# Power.net
KiCad netlist of a schematic drawn in Altium Designer
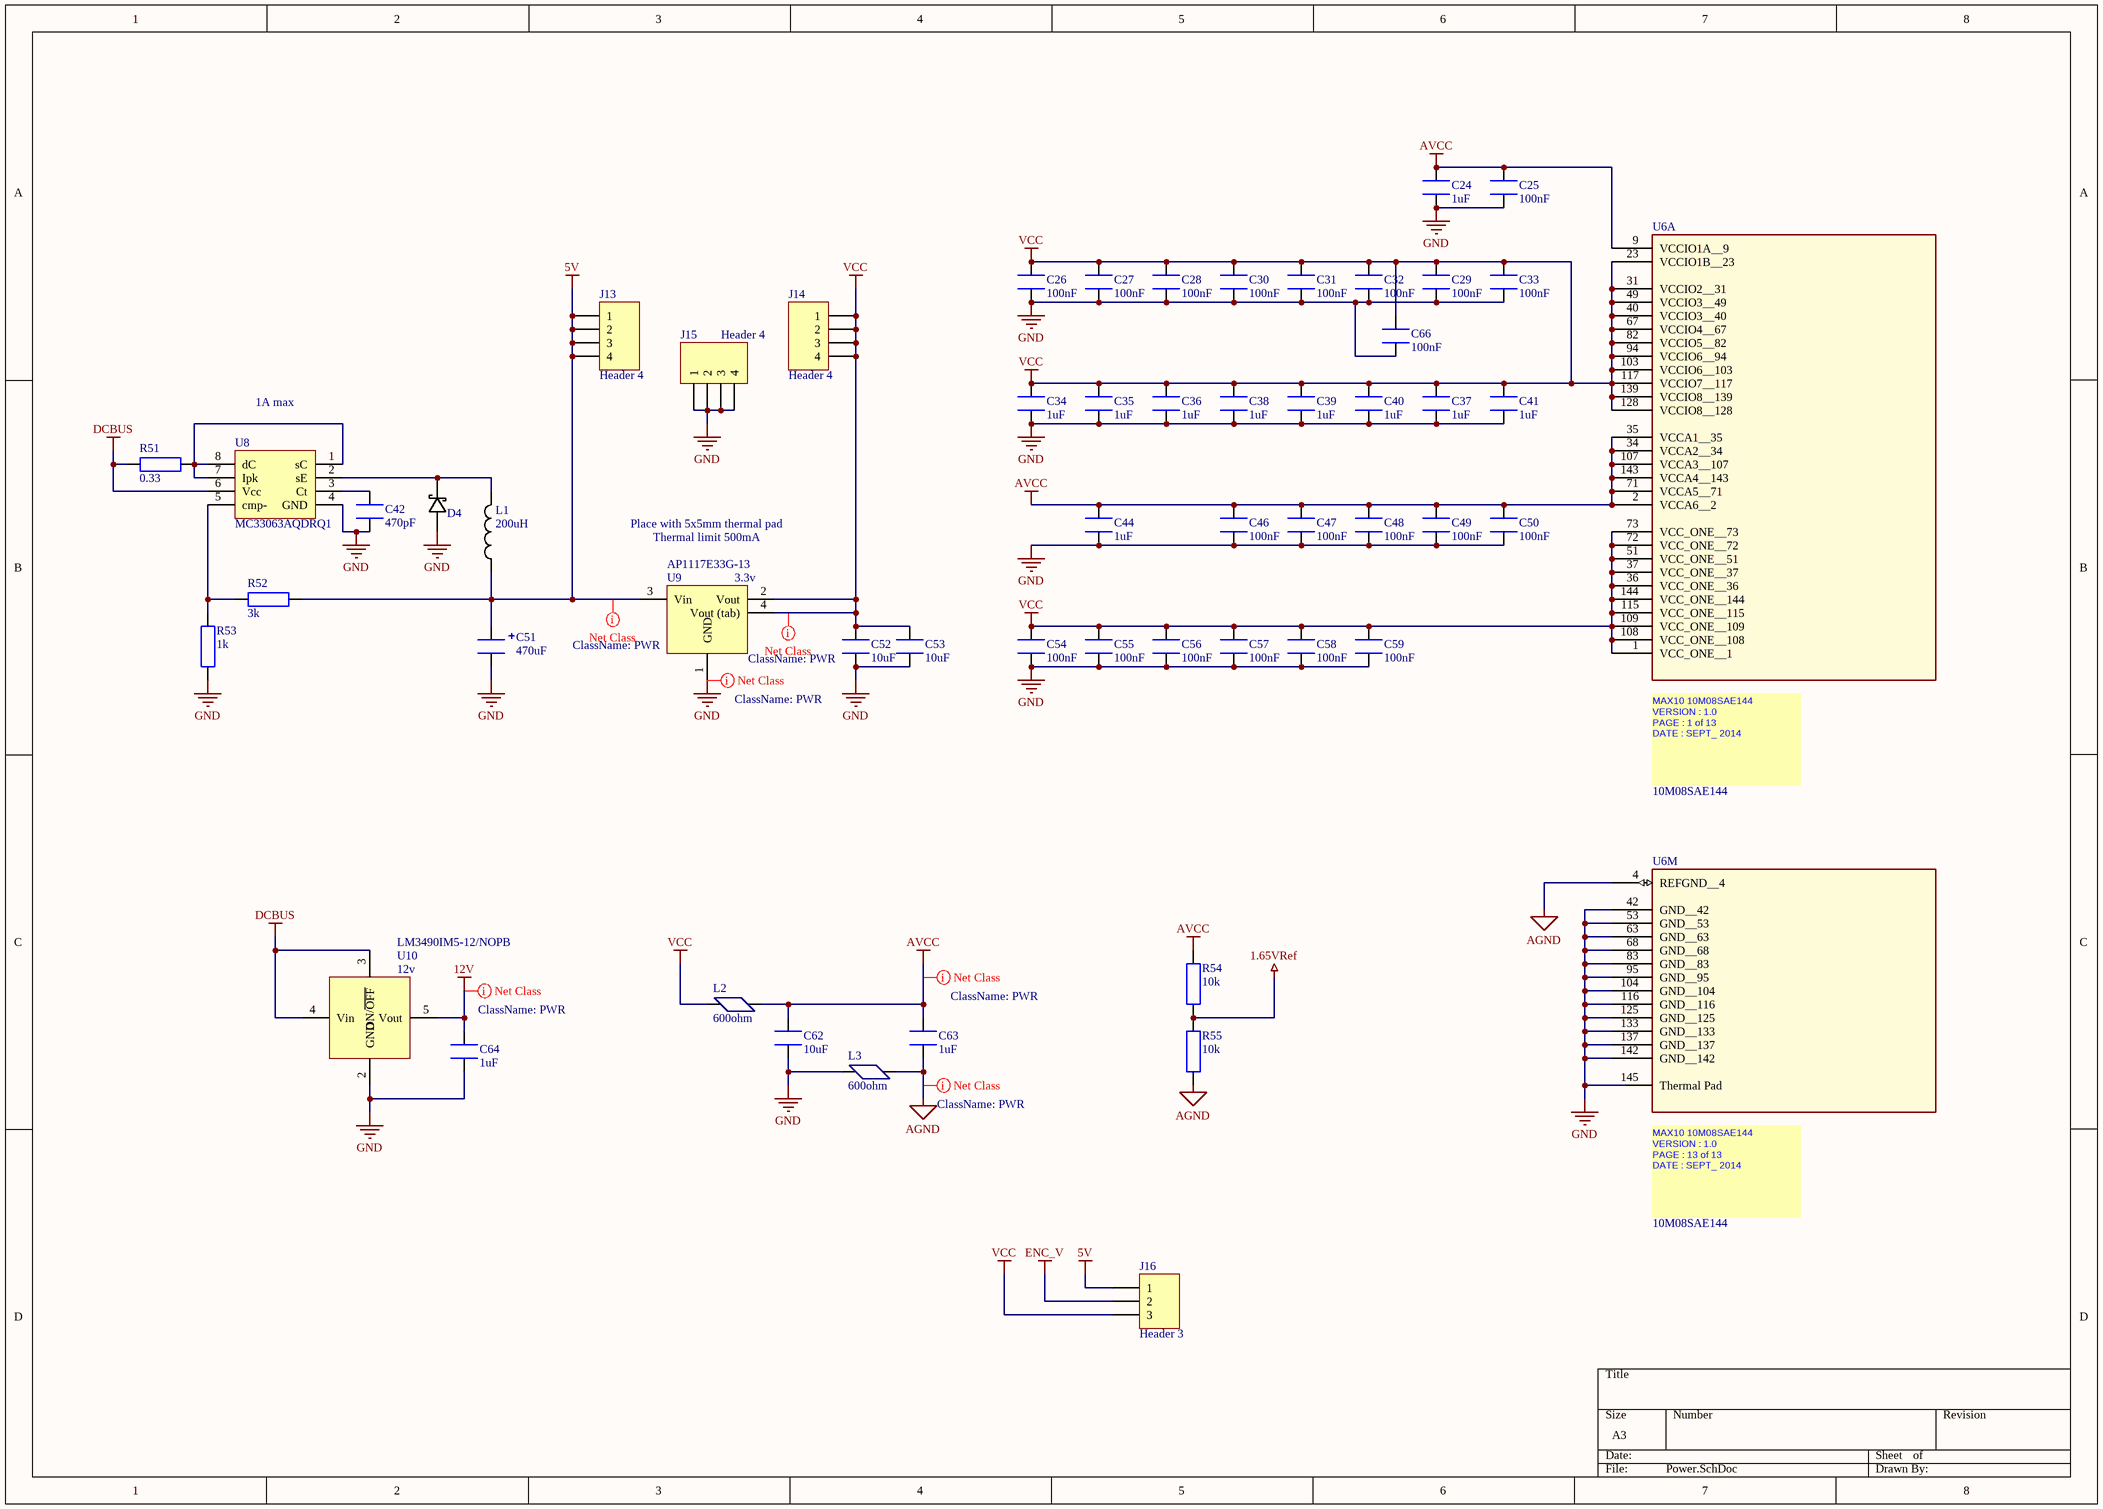
[diagram p0: Power.SchDoc]

(export (version "E")
  (design (tool "Eeschema 10.0.6"))
  (components
    (comp (ref "C24")
      (value "1uF")
      (footprint "1608[0603]")
      (description "CAP, MLCC, X5R, 1UF, 16V, 0603")
      (fields (field (name "Comment") "MC0603X105K160"))
      (libsource (lib "CustomComponents") (part "MC0603X105K160"))
    )
    (comp (ref "C25")
      (value "100nF")
      (footprint "1608[0603]")
      (description "CAP, MLCC, X7R, 100NF, 16V, 0603")
      (fields (field (name "Comment") "MC0603B104K160CT"))
      (libsource (lib "CustomComponents") (part "MC0603B104K160CT"))
    )
    (comp (ref "C26")
      (value "100nF")
      (footprint "1608[0603]")
      (description "CAP, MLCC, X7R, 100NF, 16V, 0603")
      (fields (field (name "Comment") "MC0603B104K160CT"))
      (libsource (lib "CustomComponents") (part "MC0603B104K160CT"))
    )
    (comp (ref "C27")
      (value "100nF")
      (footprint "1608[0603]")
      (description "CAP, MLCC, X7R, 100NF, 16V, 0603")
      (fields (field (name "Comment") "MC0603B104K160CT"))
      (libsource (lib "CustomComponents") (part "MC0603B104K160CT"))
    )
    (comp (ref "C28")
      (value "100nF")
      (footprint "1608[0603]")
      (description "CAP, MLCC, X7R, 100NF, 16V, 0603")
      (fields (field (name "Comment") "MC0603B104K160CT"))
      (libsource (lib "CustomComponents") (part "MC0603B104K160CT"))
    )
    (comp (ref "C29")
      (value "100nF")
      (footprint "1608[0603]")
      (description "CAP, MLCC, X7R, 100NF, 16V, 0603")
      (fields (field (name "Comment") "MC0603B104K160CT"))
      (libsource (lib "CustomComponents") (part "MC0603B104K160CT"))
    )
    (comp (ref "C30")
      (value "100nF")
      (footprint "1608[0603]")
      (description "CAP, MLCC, X7R, 100NF, 16V, 0603")
      (fields (field (name "Comment") "MC0603B104K160CT"))
      (libsource (lib "CustomComponents") (part "MC0603B104K160CT"))
    )
    (comp (ref "C31")
      (value "100nF")
      (footprint "1608[0603]")
      (description "CAP, MLCC, X7R, 100NF, 16V, 0603")
      (fields (field (name "Comment") "MC0603B104K160CT"))
      (libsource (lib "CustomComponents") (part "MC0603B104K160CT"))
    )
    (comp (ref "C32")
      (value "100nF")
      (footprint "1608[0603]")
      (description "CAP, MLCC, X7R, 100NF, 16V, 0603")
      (fields (field (name "Comment") "MC0603B104K160CT"))
      (libsource (lib "CustomComponents") (part "MC0603B104K160CT"))
    )
    (comp (ref "C33")
      (value "100nF")
      (footprint "1608[0603]")
      (description "CAP, MLCC, X7R, 100NF, 16V, 0603")
      (fields (field (name "Comment") "MC0603B104K160CT"))
      (libsource (lib "CustomComponents") (part "MC0603B104K160CT"))
    )
    (comp (ref "C34")
      (value "1uF")
      (footprint "1608[0603]")
      (description "CAP, MLCC, X5R, 1UF, 16V, 0603")
      (fields (field (name "Comment") "MC0603X105K160"))
      (libsource (lib "CustomComponents") (part "MC0603X105K160"))
    )
    (comp (ref "C35")
      (value "1uF")
      (footprint "1608[0603]")
      (description "CAP, MLCC, X5R, 1UF, 16V, 0603")
      (fields (field (name "Comment") "MC0603X105K160"))
      (libsource (lib "CustomComponents") (part "MC0603X105K160"))
    )
    (comp (ref "C36")
      (value "1uF")
      (footprint "1608[0603]")
      (description "CAP, MLCC, X5R, 1UF, 16V, 0603")
      (fields (field (name "Comment") "MC0603X105K160"))
      (libsource (lib "CustomComponents") (part "MC0603X105K160"))
    )
    (comp (ref "C37")
      (value "1uF")
      (footprint "1608[0603]")
      (description "CAP, MLCC, X5R, 1UF, 16V, 0603")
      (fields (field (name "Comment") "MC0603X105K160"))
      (libsource (lib "CustomComponents") (part "MC0603X105K160"))
    )
    (comp (ref "C38")
      (value "1uF")
      (footprint "1608[0603]")
      (description "CAP, MLCC, X5R, 1UF, 16V, 0603")
      (fields (field (name "Comment") "MC0603X105K160"))
      (libsource (lib "CustomComponents") (part "MC0603X105K160"))
    )
    (comp (ref "C39")
      (value "1uF")
      (footprint "1608[0603]")
      (description "CAP, MLCC, X5R, 1UF, 16V, 0603")
      (fields (field (name "Comment") "MC0603X105K160"))
      (libsource (lib "CustomComponents") (part "MC0603X105K160"))
    )
    (comp (ref "C40")
      (value "1uF")
      (footprint "1608[0603]")
      (description "CAP, MLCC, X5R, 1UF, 16V, 0603")
      (fields (field (name "Comment") "MC0603X105K160"))
      (libsource (lib "CustomComponents") (part "MC0603X105K160"))
    )
    (comp (ref "C41")
      (value "1uF")
      (footprint "1608[0603]")
      (description "CAP, MLCC, X5R, 1UF, 16V, 0603")
      (fields (field (name "Comment") "MC0603X105K160"))
      (libsource (lib "CustomComponents") (part "MC0603X105K160"))
    )
    (comp (ref "C42")
      (value "470pF")
      (footprint "1608[0603]")
      (description "CAP, MLCC, X7R, 470PF, 50V, 0603")
      (fields (field (name "Comment") "MC0603B471K500CT"))
      (libsource (lib "CustomComponents") (part "MC0603B471K500CT"))
    )
    (comp (ref "C44")
      (value "1uF")
      (footprint "1608[0603]")
      (description "CAP, MLCC, X5R, 1UF, 16V, 0603")
      (fields (field (name "Comment") "MC0603X105K160"))
      (libsource (lib "CustomComponents") (part "MC0603X105K160"))
    )
    (comp (ref "C46")
      (value "100nF")
      (footprint "1608[0603]")
      (description "CAP, MLCC, X7R, 100NF, 16V, 0603")
      (fields (field (name "Comment") "MC0603B104K160CT"))
      (libsource (lib "CustomComponents") (part "MC0603B104K160CT"))
    )
    (comp (ref "C47")
      (value "100nF")
      (footprint "1608[0603]")
      (description "CAP, MLCC, X7R, 100NF, 16V, 0603")
      (fields (field (name "Comment") "MC0603B104K160CT"))
      (libsource (lib "CustomComponents") (part "MC0603B104K160CT"))
    )
    (comp (ref "C48")
      (value "100nF")
      (footprint "1608[0603]")
      (description "CAP, MLCC, X7R, 100NF, 16V, 0603")
      (fields (field (name "Comment") "MC0603B104K160CT"))
      (libsource (lib "CustomComponents") (part "MC0603B104K160CT"))
    )
    (comp (ref "C49")
      (value "100nF")
      (footprint "1608[0603]")
      (description "CAP, MLCC, X7R, 100NF, 16V, 0603")
      (fields (field (name "Comment") "MC0603B104K160CT"))
      (libsource (lib "CustomComponents") (part "MC0603B104K160CT"))
    )
    (comp (ref "C50")
      (value "100nF")
      (footprint "1608[0603]")
      (description "CAP, MLCC, X7R, 100NF, 16V, 0603")
      (fields (field (name "Comment") "MC0603B104K160CT"))
      (libsource (lib "CustomComponents") (part "MC0603B104K160CT"))
    )
    (comp (ref "C51")
      (value "470uF")
      (footprint "CAP_ELEC_SIZE_G")
      (description "CAP, ALU ELEC, 470UF, 16V, SMD")
      (fields (field (name "Comment") "EEE1CA471P"))
      (libsource (lib "CustomComponents") (part "EEE1CA471P"))
    )
    (comp (ref "C52")
      (value "10uF")
      (footprint "CAPC2012X135N")
      (description "CAP, MLCC, Y5V, 10UF, 0805")
      (fields (field (name "Comment") "MC0805F106Z100CT"))
      (libsource (lib "CustomComponents") (part "MC0805F106Z100CT"))
    )
    (comp (ref "C53")
      (value "10uF")
      (footprint "CAPC2012X135N")
      (description "CAP, MLCC, Y5V, 10UF, 0805")
      (fields (field (name "Comment") "MC0805F106Z100CT"))
      (libsource (lib "CustomComponents") (part "MC0805F106Z100CT"))
    )
    (comp (ref "C54")
      (value "100nF")
      (footprint "1608[0603]")
      (description "CAP, MLCC, X7R, 100NF, 16V, 0603")
      (fields (field (name "Comment") "MC0603B104K160CT"))
      (libsource (lib "CustomComponents") (part "MC0603B104K160CT"))
    )
    (comp (ref "C55")
      (value "100nF")
      (footprint "1608[0603]")
      (description "CAP, MLCC, X7R, 100NF, 16V, 0603")
      (fields (field (name "Comment") "MC0603B104K160CT"))
      (libsource (lib "CustomComponents") (part "MC0603B104K160CT"))
    )
    (comp (ref "C56")
      (value "100nF")
      (footprint "1608[0603]")
      (description "CAP, MLCC, X7R, 100NF, 16V, 0603")
      (fields (field (name "Comment") "MC0603B104K160CT"))
      (libsource (lib "CustomComponents") (part "MC0603B104K160CT"))
    )
    (comp (ref "C57")
      (value "100nF")
      (footprint "1608[0603]")
      (description "CAP, MLCC, X7R, 100NF, 16V, 0603")
      (fields (field (name "Comment") "MC0603B104K160CT"))
      (libsource (lib "CustomComponents") (part "MC0603B104K160CT"))
    )
    (comp (ref "C58")
      (value "100nF")
      (footprint "1608[0603]")
      (description "CAP, MLCC, X7R, 100NF, 16V, 0603")
      (fields (field (name "Comment") "MC0603B104K160CT"))
      (libsource (lib "CustomComponents") (part "MC0603B104K160CT"))
    )
    (comp (ref "C59")
      (value "100nF")
      (footprint "1608[0603]")
      (description "CAP, MLCC, X7R, 100NF, 16V, 0603")
      (fields (field (name "Comment") "MC0603B104K160CT"))
      (libsource (lib "CustomComponents") (part "MC0603B104K160CT"))
    )
    (comp (ref "C62")
      (value "10uF")
      (footprint "CAPC2012X135N")
      (description "CAP, MLCC, Y5V, 10UF, 0805")
      (fields (field (name "Comment") "MC0805F106Z100CT"))
      (libsource (lib "CustomComponents") (part "MC0805F106Z100CT"))
    )
    (comp (ref "C63")
      (value "1uF")
      (footprint "1608[0603]")
      (description "CAP, MLCC, X5R, 1UF, 16V, 0603")
      (fields (field (name "Comment") "MC0603X105K160"))
      (libsource (lib "CustomComponents") (part "MC0603X105K160"))
    )
    (comp (ref "C64")
      (value "1uF")
      (footprint "1608[0603]")
      (description "CAP, MLCC, X5R, 1UF, 16V, 0603")
      (fields (field (name "Comment") "MC0603X105K160"))
      (libsource (lib "CustomComponents") (part "MC0603X105K160"))
    )
    (comp (ref "C66")
      (value "100nF")
      (footprint "1608[0603]")
      (description "CAP, MLCC, X7R, 100NF, 16V, 0603")
      (fields (field (name "Comment") "MC0603B104K160CT"))
      (libsource (lib "CustomComponents") (part "MC0603B104K160CT"))
    )
    (comp (ref "D4")
      (value "SS13B")
      (footprint "DO-214AA")
      (description "DIODE, SCHOTTK, RECTIF, 1A, 30V, SMB")
      (libsource (lib "CustomComponents") (part "SS13B"))
    )
    (comp (ref "J13")
      (value "Header 4")
      (footprint "HDR1X4")
      (description "Header, 4-Pin")
      (fields (field (name "PUBLISHER") "Altium Limited"))
      (libsource (lib "Miscellaneous Connectors") (part "Header 4"))
    )
    (comp (ref "J14")
      (value "Header 4")
      (footprint "HDR1X4")
      (description "Header, 4-Pin")
      (fields (field (name "PUBLISHER") "Altium Limited"))
      (libsource (lib "") (part "Header 4_1"))
    )
    (comp (ref "J15")
      (value "Header 4")
      (footprint "HDR1X4")
      (description "Header, 4-Pin")
      (fields (field (name "PUBLISHER") "Altium Limited"))
      (libsource (lib "") (part "Header 4_2"))
    )
    (comp (ref "J16")
      (value "Header 3")
      (footprint "HDR1X3")
      (description "Header, 3-Pin")
      (fields (field (name "PUBLISHER") "Altium Limited"))
      (libsource (lib "Miscellaneous Connectors") (part "Header 3"))
    )
    (comp (ref "L1")
      (value "200uH")
      (footprint "Inductor 12x12mm")
      (description "INDUCTOR, 220µH, 20%, 2PINS")
      (fields (field (name "Comment") "MCSDRH125B-221MHF"))
      (libsource (lib "CustomComponents") (part "MCSDRH125B-221MHF"))
    )
    (comp (ref "L2")
      (value "600ohm")
      (footprint "FBC2012N")
      (description "FERRITE BEAD, 0.1OHM, 2A, 0805")
      (fields (field (name "Comment") "2508056017Y2"))
      (libsource (lib "CustomComponents") (part "2508056017Y2"))
    )
    (comp (ref "L3")
      (value "600ohm")
      (footprint "FBC2012N")
      (description "FERRITE BEAD, 0.1OHM, 2A, 0805")
      (fields (field (name "Comment") "2508056017Y2"))
      (libsource (lib "CustomComponents") (part "2508056017Y2"))
    )
    (comp (ref "R51")
      (value "0.33")
      (footprint "RESC1608X55N")
      (description "RESISTOR, 0603, 0.1W, 1%, 0R33")
      (fields (field (name "Comment") "ERJ3RQFR33V"))
      (libsource (lib "CustomComponents") (part "ERJ3RQFR33V"))
    )
    (comp (ref "R52")
      (value "3k")
      (footprint "RESC1608X55N")
      (description "RESISTOR, 0603, 3K, 1%, ANTI SULFUR")
      (fields (field (name "Comment") "MCMR06X3001FTL"))
      (libsource (lib "CustomComponents") (part "MCMR06X3001FTL"))
    )
    (comp (ref "R53")
      (value "1k")
      (footprint "RESC1608X55N")
      (description "RESISTOR, CERAMIC, 1K, 0.1W, 1%")
      (fields (field (name "Comment") "MCMR06X1001FTL"))
      (libsource (lib "CustomComponents") (part "MCMR06X1001FTL"))
    )
    (comp (ref "R54")
      (value "10k")
      (footprint "RESC1608X06L")
      (description "Resistor, 10k, 0603")
      (fields (field (name "Comment") "MCMR06X1002FTL"))
      (libsource (lib "CustomComponents") (part "MCMR06X1002FTL"))
    )
    (comp (ref "R55")
      (value "10k")
      (footprint "RESC1608X06L")
      (description "Resistor, 10k, 0603")
      (fields (field (name "Comment") "MCMR06X1002FTL"))
      (libsource (lib "CustomComponents") (part "MCMR06X1002FTL"))
    )
    (comp (ref "U6")
      (value "10M08SAE144")
      (footprint "SQFP50P2200X2200X165_HS-145N")
      (libsource (lib "10M08SAREVERSIONTEST_Library") (part "10M08SAE144"))
    )
    (comp (ref "U8")
      (value "MC33063AQDRQ1")
      (footprint "SO8_N")
      (description "DC-DC CONV, BOOST/BUCK/INVERTING, SOIC-8")
      (libsource (lib "CustomComponents") (part "MC33063AQDRQ1"))
    )
    (comp (ref "U9")
      (value "AP1117E33G-13")
      (footprint "SOT223")
      (description "IC, LDO, REG, 3.3V, SOT223")
      (fields (field (name "ALTIUM_VALUE") "3.3v"))
      (libsource (lib "CustomComponents") (part "AP1117E33G-13"))
    )
    (comp (ref "U10")
      (value "LM3490IM5-12/NOPB")
      (footprint "SOT23-5")
      (description "LDO, FIXED, 12V, 0.1A, SOT-23-5")
      (fields (field (name "ALTIUM_VALUE") "12v"))
      (libsource (lib "CustomComponents") (part "LM3490IM5-12/NOPB"))
    )
  )
  (nets
    (net (code "1") (name "1.65VRef") (class "Default")
      (node (ref "R54") (pin "1") (pinfunction "0_1") (pintype "passive"))
      (node (ref "R55") (pin "2") (pinfunction "0_2") (pintype "passive"))
    )
    (net (code "2") (name "5V") (class "Default")
      (node (ref "C51") (pin "1") (pinfunction "1_1") (pintype "passive"))
      (node (ref "J13") (pin "1") (pinfunction "1_1") (pintype "passive"))
      (node (ref "J13") (pin "2") (pinfunction "2_2") (pintype "passive"))
      (node (ref "J13") (pin "3") (pinfunction "3_3") (pintype "passive"))
      (node (ref "J13") (pin "4") (pinfunction "4_4") (pintype "passive"))
      (node (ref "J16") (pin "1") (pinfunction "1_1") (pintype "passive"))
      (node (ref "L1") (pin "1") (pinfunction "1_1") (pintype "passive"))
      (node (ref "R52") (pin "1") (pinfunction "0_1") (pintype "passive"))
      (node (ref "U9") (pin "3") (pinfunction "Vin_3") (pintype "passive"))
    )
    (net (code "3") (name "12V") (class "Default")
      (node (ref "C64") (pin "2") (pinfunction "2_2") (pintype "passive"))
      (node (ref "U10") (pin "5") (pinfunction "Vout_5") (pintype "passive"))
    )
    (net (code "4") (name "AGND") (class "Default")
      (node (ref "C63") (pin "1") (pinfunction "1_1") (pintype "passive"))
      (node (ref "L3") (pin "1") (pinfunction "1_1") (pintype "passive"))
      (node (ref "R55") (pin "1") (pinfunction "0_1") (pintype "passive"))
      (node (ref "U6") (pin "4") (pinfunction "REFGND__4_4") (pintype "bidirectional"))
    )
    (net (code "5") (name "AVCC") (class "Default")
      (node (ref "C24") (pin "2") (pinfunction "2_2") (pintype "passive"))
      (node (ref "C25") (pin "2") (pinfunction "2_2") (pintype "passive"))
      (node (ref "C44") (pin "2") (pinfunction "2_2") (pintype "passive"))
      (node (ref "C46") (pin "2") (pinfunction "2_2") (pintype "passive"))
      (node (ref "C47") (pin "2") (pinfunction "2_2") (pintype "passive"))
      (node (ref "C48") (pin "2") (pinfunction "2_2") (pintype "passive"))
      (node (ref "C49") (pin "2") (pinfunction "2_2") (pintype "passive"))
      (node (ref "C50") (pin "2") (pinfunction "2_2") (pintype "passive"))
      (node (ref "C62") (pin "2") (pinfunction "2_2") (pintype "passive"))
      (node (ref "C63") (pin "2") (pinfunction "2_2") (pintype "passive"))
      (node (ref "L2") (pin "1") (pinfunction "1_1") (pintype "passive"))
      (node (ref "R54") (pin "2") (pinfunction "0_2") (pintype "passive"))
      (node (ref "U6") (pin "107") (pinfunction "VCCA3__107_107") (pintype "power_in"))
      (node (ref "U6") (pin "143") (pinfunction "VCCA4__143_143") (pintype "power_in"))
      (node (ref "U6") (pin "2") (pinfunction "VCCA6__2_2") (pintype "power_in"))
      (node (ref "U6") (pin "34") (pinfunction "VCCA2__34_34") (pintype "power_in"))
      (node (ref "U6") (pin "35") (pinfunction "VCCA1__35_35") (pintype "power_in"))
      (node (ref "U6") (pin "71") (pinfunction "VCCA5__71_71") (pintype "power_in"))
      (node (ref "U6") (pin "9") (pinfunction "VCCIO1A__9_9") (pintype "power_in"))
    )
    (net (code "6") (name "DCBUS") (class "Default")
      (node (ref "R51") (pin "2") (pinfunction "0_2") (pintype "passive"))
      (node (ref "U10") (pin "3") (pinfunction "ON/~{OFF}_3") (pintype "passive"))
      (node (ref "U10") (pin "4") (pinfunction "Vin_4") (pintype "passive"))
      (node (ref "U8") (pin "6") (pinfunction "Vcc_6") (pintype "passive"))
    )
    (net (code "7") (name "ENC_V") (class "Default")
      (node (ref "J16") (pin "2") (pinfunction "2_2") (pintype "passive"))
    )
    (net (code "8") (name "GND") (class "Default")
      (node (ref "C24") (pin "1") (pinfunction "1_1") (pintype "passive"))
      (node (ref "C25") (pin "1") (pinfunction "1_1") (pintype "passive"))
      (node (ref "C26") (pin "1") (pinfunction "1_1") (pintype "passive"))
      (node (ref "C27") (pin "1") (pinfunction "1_1") (pintype "passive"))
      (node (ref "C28") (pin "1") (pinfunction "1_1") (pintype "passive"))
      (node (ref "C29") (pin "1") (pinfunction "1_1") (pintype "passive"))
      (node (ref "C30") (pin "1") (pinfunction "1_1") (pintype "passive"))
      (node (ref "C31") (pin "1") (pinfunction "1_1") (pintype "passive"))
      (node (ref "C32") (pin "1") (pinfunction "1_1") (pintype "passive"))
      (node (ref "C33") (pin "1") (pinfunction "1_1") (pintype "passive"))
      (node (ref "C34") (pin "1") (pinfunction "1_1") (pintype "passive"))
      (node (ref "C35") (pin "1") (pinfunction "1_1") (pintype "passive"))
      (node (ref "C36") (pin "1") (pinfunction "1_1") (pintype "passive"))
      (node (ref "C37") (pin "1") (pinfunction "1_1") (pintype "passive"))
      (node (ref "C38") (pin "1") (pinfunction "1_1") (pintype "passive"))
      (node (ref "C39") (pin "1") (pinfunction "1_1") (pintype "passive"))
      (node (ref "C40") (pin "1") (pinfunction "1_1") (pintype "passive"))
      (node (ref "C41") (pin "1") (pinfunction "1_1") (pintype "passive"))
      (node (ref "C42") (pin "1") (pinfunction "1_1") (pintype "passive"))
      (node (ref "C44") (pin "1") (pinfunction "1_1") (pintype "passive"))
      (node (ref "C46") (pin "1") (pinfunction "1_1") (pintype "passive"))
      (node (ref "C47") (pin "1") (pinfunction "1_1") (pintype "passive"))
      (node (ref "C48") (pin "1") (pinfunction "1_1") (pintype "passive"))
      (node (ref "C49") (pin "1") (pinfunction "1_1") (pintype "passive"))
      (node (ref "C50") (pin "1") (pinfunction "1_1") (pintype "passive"))
      (node (ref "C51") (pin "2") (pinfunction "2_2") (pintype "passive"))
      (node (ref "C52") (pin "1") (pinfunction "1_1") (pintype "passive"))
      (node (ref "C53") (pin "1") (pinfunction "1_1") (pintype "passive"))
      (node (ref "C54") (pin "1") (pinfunction "1_1") (pintype "passive"))
      (node (ref "C55") (pin "1") (pinfunction "1_1") (pintype "passive"))
      (node (ref "C56") (pin "1") (pinfunction "1_1") (pintype "passive"))
      (node (ref "C57") (pin "1") (pinfunction "1_1") (pintype "passive"))
      (node (ref "C58") (pin "1") (pinfunction "1_1") (pintype "passive"))
      (node (ref "C59") (pin "1") (pinfunction "1_1") (pintype "passive"))
      (node (ref "C62") (pin "1") (pinfunction "1_1") (pintype "passive"))
      (node (ref "C64") (pin "1") (pinfunction "1_1") (pintype "passive"))
      (node (ref "C66") (pin "1") (pinfunction "1_1") (pintype "passive"))
      (node (ref "D4") (pin "A") (pinfunction "A_A") (pintype "passive"))
      (node (ref "J15") (pin "1") (pinfunction "1_1") (pintype "passive"))
      (node (ref "J15") (pin "2") (pinfunction "2_2") (pintype "passive"))
      (node (ref "J15") (pin "3") (pinfunction "3_3") (pintype "passive"))
      (node (ref "J15") (pin "4") (pinfunction "4_4") (pintype "passive"))
      (node (ref "L3") (pin "2") (pinfunction "2_2") (pintype "passive"))
      (node (ref "R53") (pin "1") (pinfunction "0_1") (pintype "passive"))
      (node (ref "U10") (pin "2") (pinfunction "GND_2") (pintype "passive"))
      (node (ref "U6") (pin "104") (pinfunction "GND__104_104") (pintype "power_in"))
      (node (ref "U6") (pin "116") (pinfunction "GND__116_116") (pintype "power_in"))
      (node (ref "U6") (pin "125") (pinfunction "GND__125_125") (pintype "power_in"))
      (node (ref "U6") (pin "133") (pinfunction "GND__133_133") (pintype "power_in"))
      (node (ref "U6") (pin "137") (pinfunction "GND__137_137") (pintype "power_in"))
      (node (ref "U6") (pin "142") (pinfunction "GND__142_142") (pintype "power_in"))
      (node (ref "U6") (pin "145") (pinfunction "Thermal_Pad_145") (pintype "passive"))
      (node (ref "U6") (pin "42") (pinfunction "GND__42_42") (pintype "power_in"))
      (node (ref "U6") (pin "53") (pinfunction "GND__53_53") (pintype "power_in"))
      (node (ref "U6") (pin "63") (pinfunction "GND__63_63") (pintype "power_in"))
      (node (ref "U6") (pin "68") (pinfunction "GND__68_68") (pintype "power_in"))
      (node (ref "U6") (pin "83") (pinfunction "GND__83_83") (pintype "power_in"))
      (node (ref "U6") (pin "95") (pinfunction "GND__95_95") (pintype "power_in"))
      (node (ref "U8") (pin "4") (pinfunction "GND_4") (pintype "passive"))
      (node (ref "U9") (pin "1") (pinfunction "GND_1") (pintype "passive"))
    )
    (net (code "9") (name "Net-(U8-Ct)") (class "Default")
      (node (ref "C42") (pin "2") (pinfunction "2_2") (pintype "passive"))
      (node (ref "U8") (pin "3") (pinfunction "Ct_3") (pintype "passive"))
    )
    (net (code "10") (name "Net-(U8-Ipk)") (class "Default")
      (node (ref "R51") (pin "1") (pinfunction "0_1") (pintype "passive"))
      (node (ref "U8") (pin "1") (pinfunction "sC_1") (pintype "passive"))
      (node (ref "U8") (pin "7") (pinfunction "Ipk_7") (pintype "passive"))
      (node (ref "U8") (pin "8") (pinfunction "dC_8") (pintype "passive"))
    )
    (net (code "11") (name "Net-(U8-cmp-)") (class "Default")
      (node (ref "R52") (pin "2") (pinfunction "0_2") (pintype "passive"))
      (node (ref "R53") (pin "2") (pinfunction "0_2") (pintype "passive"))
      (node (ref "U8") (pin "5") (pinfunction "cmp-_5") (pintype "passive"))
    )
    (net (code "12") (name "Net-(U8-sE)") (class "Default")
      (node (ref "D4") (pin "K") (pinfunction "K_K") (pintype "passive"))
      (node (ref "L1") (pin "2") (pinfunction "2_2") (pintype "passive"))
      (node (ref "U8") (pin "2") (pinfunction "sE_2") (pintype "passive"))
    )
    (net (code "13") (name "VCC") (class "Default")
      (node (ref "C26") (pin "2") (pinfunction "2_2") (pintype "passive"))
      (node (ref "C27") (pin "2") (pinfunction "2_2") (pintype "passive"))
      (node (ref "C28") (pin "2") (pinfunction "2_2") (pintype "passive"))
      (node (ref "C29") (pin "2") (pinfunction "2_2") (pintype "passive"))
      (node (ref "C30") (pin "2") (pinfunction "2_2") (pintype "passive"))
      (node (ref "C31") (pin "2") (pinfunction "2_2") (pintype "passive"))
      (node (ref "C32") (pin "2") (pinfunction "2_2") (pintype "passive"))
      (node (ref "C33") (pin "2") (pinfunction "2_2") (pintype "passive"))
      (node (ref "C34") (pin "2") (pinfunction "2_2") (pintype "passive"))
      (node (ref "C35") (pin "2") (pinfunction "2_2") (pintype "passive"))
      (node (ref "C36") (pin "2") (pinfunction "2_2") (pintype "passive"))
      (node (ref "C37") (pin "2") (pinfunction "2_2") (pintype "passive"))
      (node (ref "C38") (pin "2") (pinfunction "2_2") (pintype "passive"))
      (node (ref "C39") (pin "2") (pinfunction "2_2") (pintype "passive"))
      (node (ref "C40") (pin "2") (pinfunction "2_2") (pintype "passive"))
      (node (ref "C41") (pin "2") (pinfunction "2_2") (pintype "passive"))
      (node (ref "C52") (pin "2") (pinfunction "2_2") (pintype "passive"))
      (node (ref "C53") (pin "2") (pinfunction "2_2") (pintype "passive"))
      (node (ref "C54") (pin "2") (pinfunction "2_2") (pintype "passive"))
      (node (ref "C55") (pin "2") (pinfunction "2_2") (pintype "passive"))
      (node (ref "C56") (pin "2") (pinfunction "2_2") (pintype "passive"))
      (node (ref "C57") (pin "2") (pinfunction "2_2") (pintype "passive"))
      (node (ref "C58") (pin "2") (pinfunction "2_2") (pintype "passive"))
      (node (ref "C59") (pin "2") (pinfunction "2_2") (pintype "passive"))
      (node (ref "C66") (pin "2") (pinfunction "2_2") (pintype "passive"))
      (node (ref "J14") (pin "1") (pinfunction "1_1") (pintype "passive"))
      (node (ref "J14") (pin "2") (pinfunction "2_2") (pintype "passive"))
      (node (ref "J14") (pin "3") (pinfunction "3_3") (pintype "passive"))
      (node (ref "J14") (pin "4") (pinfunction "4_4") (pintype "passive"))
      (node (ref "J16") (pin "3") (pinfunction "3_3") (pintype "passive"))
      (node (ref "L2") (pin "2") (pinfunction "2_2") (pintype "passive"))
      (node (ref "U6") (pin "1") (pinfunction "VCC_ONE__1_1") (pintype "power_in"))
      (node (ref "U6") (pin "103") (pinfunction "VCCIO6__103_103") (pintype "power_in"))
      (node (ref "U6") (pin "108") (pinfunction "VCC_ONE__108_108") (pintype "power_in"))
      (node (ref "U6") (pin "109") (pinfunction "VCC_ONE__109_109") (pintype "power_in"))
      (node (ref "U6") (pin "115") (pinfunction "VCC_ONE__115_115") (pintype "power_in"))
      (node (ref "U6") (pin "117") (pinfunction "VCCIO7__117_117") (pintype "power_in"))
      (node (ref "U6") (pin "128") (pinfunction "VCCIO8__128_128") (pintype "power_in"))
      (node (ref "U6") (pin "139") (pinfunction "VCCIO8__139_139") (pintype "power_in"))
      (node (ref "U6") (pin "144") (pinfunction "VCC_ONE__144_144") (pintype "power_in"))
      (node (ref "U6") (pin "23") (pinfunction "VCCIO1B__23_23") (pintype "power_in"))
      (node (ref "U6") (pin "31") (pinfunction "VCCIO2__31_31") (pintype "power_in"))
      (node (ref "U6") (pin "36") (pinfunction "VCC_ONE__36_36") (pintype "power_in"))
      (node (ref "U6") (pin "37") (pinfunction "VCC_ONE__37_37") (pintype "power_in"))
      (node (ref "U6") (pin "40") (pinfunction "VCCIO3__40_40") (pintype "power_in"))
      (node (ref "U6") (pin "49") (pinfunction "VCCIO3__49_49") (pintype "power_in"))
      (node (ref "U6") (pin "51") (pinfunction "VCC_ONE__51_51") (pintype "power_in"))
      (node (ref "U6") (pin "67") (pinfunction "VCCIO4__67_67") (pintype "power_in"))
      (node (ref "U6") (pin "72") (pinfunction "VCC_ONE__72_72") (pintype "power_in"))
      (node (ref "U6") (pin "73") (pinfunction "VCC_ONE__73_73") (pintype "power_in"))
      (node (ref "U6") (pin "82") (pinfunction "VCCIO5__82_82") (pintype "power_in"))
      (node (ref "U6") (pin "94") (pinfunction "VCCIO6__94_94") (pintype "power_in"))
      (node (ref "U9") (pin "2") (pinfunction "Vout_2") (pintype "passive"))
      (node (ref "U9") (pin "4") (pinfunction "Vout_(tab)_4") (pintype "passive"))
    )
  )
)
